# SC70-6-normal.net
KiCad netlist of a schematic drawn in EAGLE
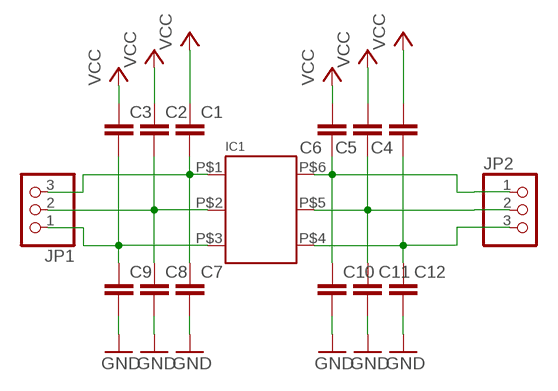
[diagram p0: schematic, sheet 1]

(export (version "E")
  (design (tool "Eeschema 10.0.6"))
  (components
    (comp (ref "C1")
      (value "C-EUC0805")
      (footprint "eagle-import:C0805")
      (libsource (lib "eagle-import") (part "C-EUC0805"))
    )
    (comp (ref "C2")
      (value "C-EUC0805")
      (footprint "eagle-import:C0805")
      (libsource (lib "eagle-import") (part "C-EUC0805"))
    )
    (comp (ref "C3")
      (value "C-EUC0805")
      (footprint "eagle-import:C0805")
      (libsource (lib "eagle-import") (part "C-EUC0805"))
    )
    (comp (ref "C4")
      (value "C-EUC0805")
      (footprint "eagle-import:C0805")
      (libsource (lib "eagle-import") (part "C-EUC0805"))
    )
    (comp (ref "C5")
      (value "C-EUC0805")
      (footprint "eagle-import:C0805")
      (libsource (lib "eagle-import") (part "C-EUC0805"))
    )
    (comp (ref "C6")
      (value "C-EUC0805")
      (footprint "eagle-import:C0805")
      (libsource (lib "eagle-import") (part "C-EUC0805"))
    )
    (comp (ref "C7")
      (value "C-EUC0603")
      (footprint "eagle-import:C0603")
      (libsource (lib "eagle-import") (part "C-EUC0603"))
    )
    (comp (ref "C8")
      (value "C-EUC0603")
      (footprint "eagle-import:C0603")
      (libsource (lib "eagle-import") (part "C-EUC0603"))
    )
    (comp (ref "C9")
      (value "C-EUC0603")
      (footprint "eagle-import:C0603")
      (libsource (lib "eagle-import") (part "C-EUC0603"))
    )
    (comp (ref "C10")
      (value "C-EUC0603")
      (footprint "eagle-import:C0603")
      (libsource (lib "eagle-import") (part "C-EUC0603"))
    )
    (comp (ref "C11")
      (value "C-EUC0603")
      (footprint "eagle-import:C0603")
      (libsource (lib "eagle-import") (part "C-EUC0603"))
    )
    (comp (ref "C12")
      (value "C-EUC0603")
      (footprint "eagle-import:C0603")
      (libsource (lib "eagle-import") (part "C-EUC0603"))
    )
    (comp (ref "IC1")
      (value "FOOTPRINT-6-PINSC70")
      (footprint "eagle-import:SC-70_6")
      (libsource (lib "eagle-import") (part "FOOTPRINT-6-PINSC70"))
    )
    (comp (ref "JP1")
      (value "PINHD-1X3")
      (footprint "eagle-import:1X03")
      (libsource (lib "eagle-import") (part "PINHD-1X3"))
    )
    (comp (ref "JP2")
      (value "PINHD-1X3")
      (footprint "eagle-import:1X03")
      (libsource (lib "eagle-import") (part "PINHD-1X3"))
    )
  )
  (nets
    (net (code "1") (name "GND") (class "Default")
      (node (ref "C10") (pin "2") (pinfunction "2_2") (pintype "passive"))
      (node (ref "C11") (pin "2") (pinfunction "2_2") (pintype "passive"))
      (node (ref "C12") (pin "2") (pinfunction "2_2") (pintype "passive"))
      (node (ref "C7") (pin "2") (pinfunction "2_2") (pintype "passive"))
      (node (ref "C8") (pin "2") (pinfunction "2_2") (pintype "passive"))
      (node (ref "C9") (pin "2") (pinfunction "2_2") (pintype "passive"))
    )
    (net (code "2") (name "Net-(IC1-1)") (class "Default")
      (node (ref "C1") (pin "2") (pinfunction "2_2") (pintype "passive"))
      (node (ref "C7") (pin "1") (pinfunction "1_1") (pintype "passive"))
      (node (ref "IC1") (pin "P$1") (pinfunction "1_P$1") (pintype "bidirectional"))
      (node (ref "JP1") (pin "3") (pinfunction "3_3") (pintype "passive"))
    )
    (net (code "3") (name "Net-(IC1-2)") (class "Default")
      (node (ref "C2") (pin "2") (pinfunction "2_2") (pintype "passive"))
      (node (ref "C8") (pin "1") (pinfunction "1_1") (pintype "passive"))
      (node (ref "IC1") (pin "P$2") (pinfunction "2_P$2") (pintype "bidirectional"))
      (node (ref "JP1") (pin "2") (pinfunction "2_2") (pintype "passive"))
    )
    (net (code "4") (name "Net-(IC1-3)") (class "Default")
      (node (ref "C3") (pin "2") (pinfunction "2_2") (pintype "passive"))
      (node (ref "C9") (pin "1") (pinfunction "1_1") (pintype "passive"))
      (node (ref "IC1") (pin "P$3") (pinfunction "3_P$3") (pintype "bidirectional"))
      (node (ref "JP1") (pin "1") (pinfunction "1_1") (pintype "passive"))
    )
    (net (code "5") (name "Net-(IC1-4)") (class "Default")
      (node (ref "C12") (pin "1") (pinfunction "1_1") (pintype "passive"))
      (node (ref "C4") (pin "1") (pinfunction "1_1") (pintype "passive"))
      (node (ref "IC1") (pin "P$4") (pinfunction "4_P$4") (pintype "bidirectional"))
      (node (ref "JP2") (pin "3") (pinfunction "3_3") (pintype "passive"))
    )
    (net (code "6") (name "Net-(IC1-5)") (class "Default")
      (node (ref "C11") (pin "1") (pinfunction "1_1") (pintype "passive"))
      (node (ref "C5") (pin "1") (pinfunction "1_1") (pintype "passive"))
      (node (ref "IC1") (pin "P$5") (pinfunction "5_P$5") (pintype "bidirectional"))
      (node (ref "JP2") (pin "2") (pinfunction "2_2") (pintype "passive"))
    )
    (net (code "7") (name "Net-(IC1-6)") (class "Default")
      (node (ref "C10") (pin "1") (pinfunction "1_1") (pintype "passive"))
      (node (ref "C6") (pin "1") (pinfunction "1_1") (pintype "passive"))
      (node (ref "IC1") (pin "P$6") (pinfunction "6_P$6") (pintype "bidirectional"))
      (node (ref "JP2") (pin "1") (pinfunction "1_1") (pintype "passive"))
    )
    (net (code "8") (name "VCC") (class "Default")
      (node (ref "C1") (pin "1") (pinfunction "1_1") (pintype "passive"))
      (node (ref "C2") (pin "1") (pinfunction "1_1") (pintype "passive"))
      (node (ref "C3") (pin "1") (pinfunction "1_1") (pintype "passive"))
      (node (ref "C4") (pin "2") (pinfunction "2_2") (pintype "passive"))
      (node (ref "C5") (pin "2") (pinfunction "2_2") (pintype "passive"))
      (node (ref "C6") (pin "2") (pinfunction "2_2") (pintype "passive"))
    )
  )
)
